# EEPROM.net
KiCad netlist of a schematic drawn in Altium Designer
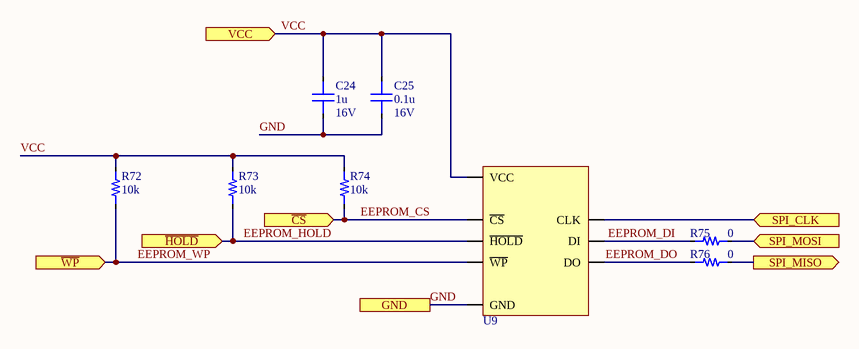
[diagram p0: EEPROM.SchDoc]

(export (version "E")
  (design (tool "Eeschema 10.0.6"))
  (components
    (comp (ref "C24")
      (value "1u")
      (footprint "0603_CAP")
      (fields (field (name "VOLTAGE") "16V") (field (name "Comment") "Capacitor"))
      (libsource (lib "Capacitors") (part "Capacitor"))
    )
    (comp (ref "C25")
      (value "0.1u")
      (footprint "0603_CAP")
      (fields (field (name "VOLTAGE") "16V") (field (name "Comment") "Capacitor"))
      (libsource (lib "Capacitors") (part "Capacitor"))
    )
    (comp (ref "R72")
      (value "10k")
      (footprint "0603_RES")
      (fields (field (name "Comment") "Resistor"))
      (libsource (lib "Resistors") (part "Resistor"))
    )
    (comp (ref "R73")
      (value "10k")
      (footprint "0603_RES")
      (fields (field (name "Comment") "Resistor"))
      (libsource (lib "Resistors") (part "Resistor"))
    )
    (comp (ref "R74")
      (value "10k")
      (footprint "0603_RES")
      (fields (field (name "Comment") "Resistor"))
      (libsource (lib "Resistors") (part "Resistor"))
    )
    (comp (ref "R75")
      (value "0")
      (footprint "0603_RES")
      (fields (field (name "Comment") "Resistor"))
      (libsource (lib "Resistors") (part "Resistor"))
    )
    (comp (ref "R76")
      (value "0")
      (footprint "0603_RES")
      (fields (field (name "Comment") "Resistor"))
      (libsource (lib "Resistors") (part "Resistor"))
    )
    (comp (ref "U9")
      (value "W25X40CL")
      (footprint "SOIC-8")
      (description "FLASH Memory IC 4Mbit SPI 104 MHz 8-SOIC")
      (fields (field (name "VOLTAGE") "5"))
      (libsource (lib "Digital_IC") (part "W25X40CL"))
    )
  )
  (nets
    (net (code "1") (name "/EEPROM_CS") (class "Default")
      (node (ref "R74") (pin "1") (pinfunction "1_1") (pintype "passive"))
      (node (ref "U9") (pin "1") (pinfunction "~{CS}_1") (pintype "passive"))
    )
    (net (code "2") (name "/EEPROM_DI") (class "Default")
      (node (ref "R75") (pin "1") (pinfunction "1_1") (pintype "passive"))
      (node (ref "U9") (pin "5") (pinfunction "DI_5") (pintype "passive"))
    )
    (net (code "3") (name "/EEPROM_DO") (class "Default")
      (node (ref "R76") (pin "1") (pinfunction "1_1") (pintype "passive"))
      (node (ref "U9") (pin "2") (pinfunction "DO_2") (pintype "passive"))
    )
    (net (code "4") (name "/EEPROM_HOLD") (class "Default")
      (node (ref "R73") (pin "1") (pinfunction "1_1") (pintype "passive"))
      (node (ref "U9") (pin "7") (pinfunction "~{HOLD}_7") (pintype "passive"))
    )
    (net (code "5") (name "/EEPROM_WP") (class "Default")
      (node (ref "R72") (pin "1") (pinfunction "1_1") (pintype "passive"))
      (node (ref "U9") (pin "3") (pinfunction "~{WP}_3") (pintype "passive"))
    )
    (net (code "6") (name "/GND") (class "Default")
      (node (ref "C24") (pin "1") (pinfunction "1_1") (pintype "passive"))
      (node (ref "C25") (pin "1") (pinfunction "1_1") (pintype "passive"))
      (node (ref "U9") (pin "4") (pinfunction "GND_4") (pintype "passive"))
    )
    (net (code "7") (name "/SPI_CLK") (class "Default")
      (node (ref "U9") (pin "6") (pinfunction "CLK_6") (pintype "passive"))
    )
    (net (code "8") (name "/SPI_MISO") (class "Default")
      (node (ref "R76") (pin "2") (pinfunction "2_2") (pintype "passive"))
    )
    (net (code "9") (name "/SPI_MOSI") (class "Default")
      (node (ref "R75") (pin "2") (pinfunction "2_2") (pintype "passive"))
    )
    (net (code "10") (name "/VCC") (class "Default")
      (node (ref "C24") (pin "2") (pinfunction "2_2") (pintype "passive"))
      (node (ref "C25") (pin "2") (pinfunction "2_2") (pintype "passive"))
      (node (ref "R72") (pin "2") (pinfunction "2_2") (pintype "passive"))
      (node (ref "R73") (pin "2") (pinfunction "2_2") (pintype "passive"))
      (node (ref "R74") (pin "2") (pinfunction "2_2") (pintype "passive"))
      (node (ref "U9") (pin "8") (pinfunction "VCC_8") (pintype "passive"))
    )
  )
)
